# Load_Cell_Biasing.net
KiCad netlist of a schematic drawn in Altium Designer
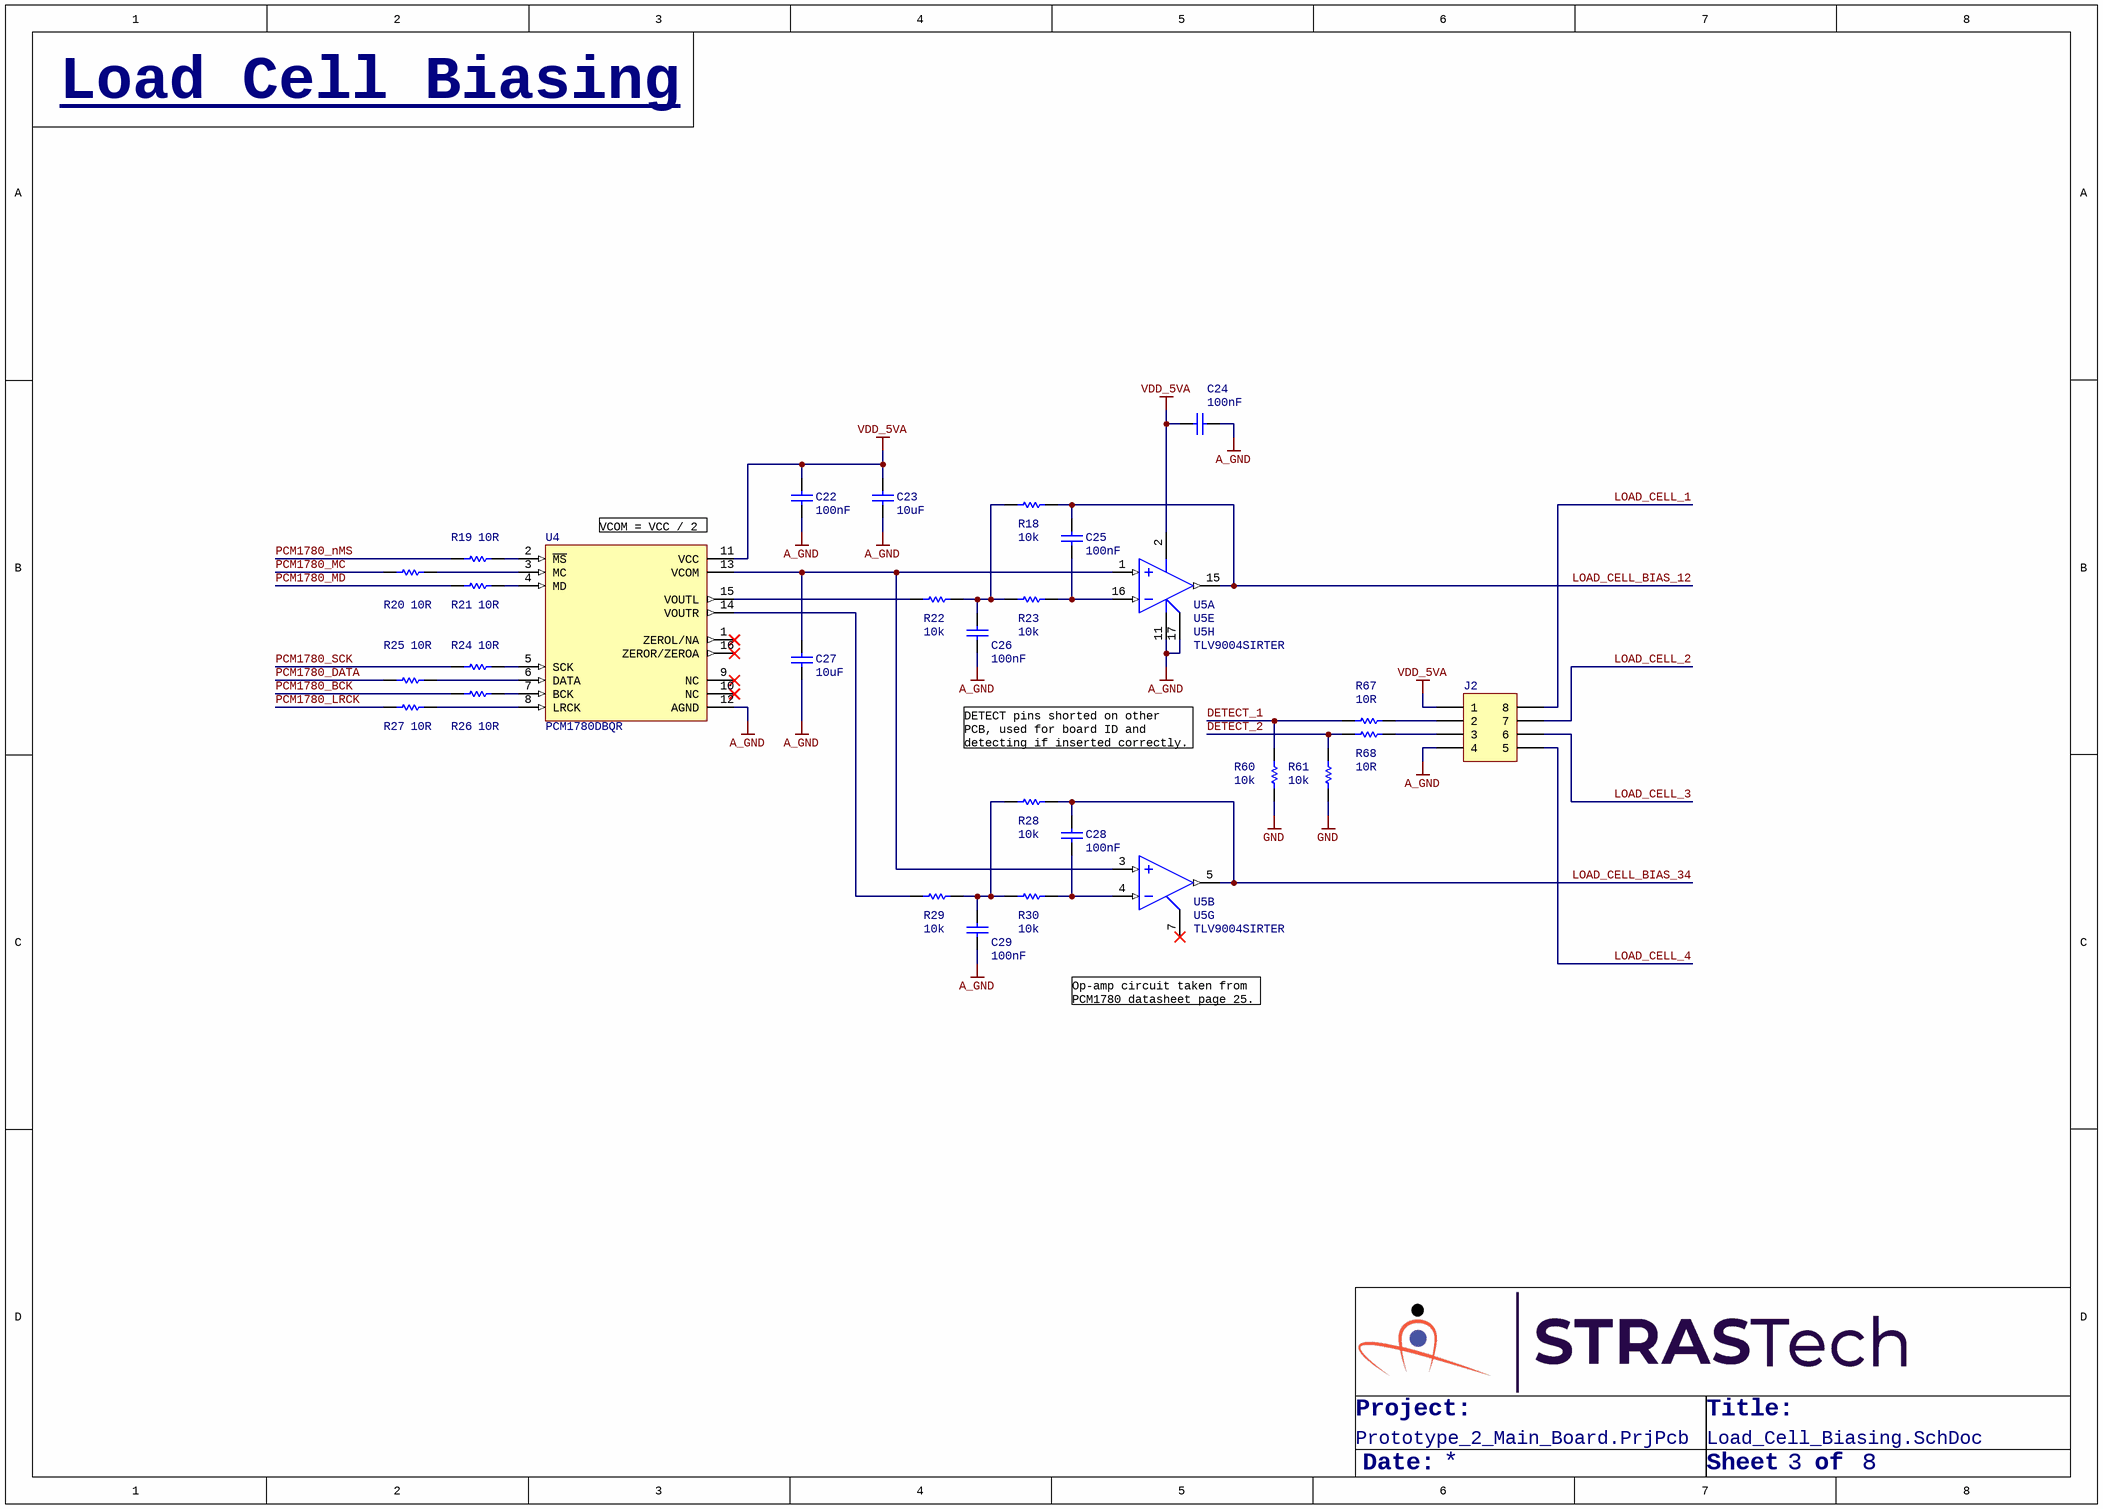
[diagram p0: Load_Cell_Biasing.SchDoc]

(export (version "E")
  (design (tool "Eeschema 10.0.6"))
  (components
    (comp (ref "C22")
      (value "100nF")
      (footprint "Cap,SMD,0402")
      (description "0.1µF ±10% 25V Ceramic Capacitor X7R 0402 (1005 Metric)")
      (fields
        (field (name "VENDOR PART NUMBER") "490-14603-1-ND")
        (field (name "MANUFACTURER") "Murata Electronics")
        (field (name "CREATEDBY") "Judd Foster")
      )
      (libsource (lib "symbols") (part "CAP,Cer,100nF,25VDC,X7R,0402"))
    )
    (comp (ref "C23")
      (value "10uF")
      (footprint "Cap,SMD,0402")
      (description "10 µF ±20% 10V Ceramic Capacitor X5R 0402 (1005 Metric)")
      (fields
        (field (name "VENDOR PART NUMBER") "1276-1450-1-ND")
        (field (name "MANUFACTURER") "Samsung Electro-Mechanics")
        (field (name "CREATEDBY") "Judd Foster")
      )
      (libsource (lib "symbols") (part "CAP,Cer,10uF,10VDC,X5R,0402"))
    )
    (comp (ref "C24")
      (value "100nF")
      (footprint "Cap,SMD,0402")
      (description "0.1µF ±10% 25V Ceramic Capacitor X7R 0402 (1005 Metric)")
      (fields
        (field (name "VENDOR PART NUMBER") "490-14603-1-ND")
        (field (name "MANUFACTURER") "Murata Electronics")
        (field (name "CREATEDBY") "Judd Foster")
      )
      (libsource (lib "symbols") (part "CAP,Cer,100nF,25VDC,X7R,0402"))
    )
    (comp (ref "C25")
      (value "100nF")
      (footprint "Cap,SMD,0402")
      (description "0.1µF ±10% 25V Ceramic Capacitor X7R 0402 (1005 Metric)")
      (fields
        (field (name "VENDOR PART NUMBER") "490-14603-1-ND")
        (field (name "MANUFACTURER") "Murata Electronics")
        (field (name "CREATEDBY") "Judd Foster")
      )
      (libsource (lib "symbols") (part "CAP,Cer,100nF,25VDC,X7R,0402"))
    )
    (comp (ref "C26")
      (value "100nF")
      (footprint "Cap,SMD,0402")
      (description "0.1µF ±10% 25V Ceramic Capacitor X7R 0402 (1005 Metric)")
      (fields
        (field (name "VENDOR PART NUMBER") "490-14603-1-ND")
        (field (name "MANUFACTURER") "Murata Electronics")
        (field (name "CREATEDBY") "Judd Foster")
      )
      (libsource (lib "symbols") (part "CAP,Cer,100nF,25VDC,X7R,0402"))
    )
    (comp (ref "C27")
      (value "10uF")
      (footprint "Cap,SMD,0402")
      (description "10 µF ±20% 10V Ceramic Capacitor X5R 0402 (1005 Metric)")
      (fields
        (field (name "VENDOR PART NUMBER") "1276-1450-1-ND")
        (field (name "MANUFACTURER") "Samsung Electro-Mechanics")
        (field (name "CREATEDBY") "Judd Foster")
      )
      (libsource (lib "symbols") (part "CAP,Cer,10uF,10VDC,X5R,0402"))
    )
    (comp (ref "C28")
      (value "100nF")
      (footprint "Cap,SMD,0402")
      (description "0.1µF ±10% 25V Ceramic Capacitor X7R 0402 (1005 Metric)")
      (fields
        (field (name "VENDOR PART NUMBER") "490-14603-1-ND")
        (field (name "MANUFACTURER") "Murata Electronics")
        (field (name "CREATEDBY") "Judd Foster")
      )
      (libsource (lib "symbols") (part "CAP,Cer,100nF,25VDC,X7R,0402"))
    )
    (comp (ref "C29")
      (value "100nF")
      (footprint "Cap,SMD,0402")
      (description "0.1µF ±10% 25V Ceramic Capacitor X7R 0402 (1005 Metric)")
      (fields
        (field (name "VENDOR PART NUMBER") "490-14603-1-ND")
        (field (name "MANUFACTURER") "Murata Electronics")
        (field (name "CREATEDBY") "Judd Foster")
      )
      (libsource (lib "symbols") (part "CAP,Cer,100nF,25VDC,X7R,0402"))
    )
    (comp (ref "J2")
      (value "Conn,Spring,Piston,8Pos,Thru")
      (footprint "Conn,Spring,Piston,8Pos,Thru")
      (description "8 Position Spring Piston Connector Through Hole")
      (fields
        (field (name "MANUFACTURER") "Mill-Max Manufacturing Corp.")
        (field (name "MANUFACTURER PART NUMBER") "823-22-008-10-002101")
        (field (name "CREATEDBY") "Judd Foster")
      )
      (libsource (lib "symbols") (part "Conn,Spring,Piston,8Pos,Thru"))
    )
    (comp (ref "R18")
      (value "10k")
      (footprint "RES,0402")
      (description "10 kOhms ±5% 0.063W, 1/16W Chip Resistor 0402 (1005 Metric) Automotive AEC-Q200 Thick Film")
      (fields
        (field (name "VENDOR PART NUMBER") "RMCF0402JT10K0CT-ND")
        (field (name "MANUFACTURER") "Stackpole Electronics Inc")
        (field (name "CREATEDBY") "Judd Foster")
      )
      (libsource (lib "symbols") (part "RES,10k,5%,0.063W,0402"))
    )
    (comp (ref "R19")
      (value "10R")
      (footprint "RES,0402")
      (description "10 Ohms ±1% 0.063W, 1/16W Chip Resistor 0402 (1005 Metric) Automotive AEC-Q200 Thick Film")
      (fields
        (field (name "MANUFACTURER") "Panasonic Electronic Components")
        (field (name "MANUFACTURER PART NUMBER") "ERJ-2RKF10R0X")
        (field (name "CREATEDBY") "Judd Foster")
      )
      (libsource (lib "symbols") (part "RES,10R,1%,0.063W,0402"))
    )
    (comp (ref "R20")
      (value "10R")
      (footprint "RES,0402")
      (description "10 Ohms ±1% 0.063W, 1/16W Chip Resistor 0402 (1005 Metric) Automotive AEC-Q200 Thick Film")
      (fields
        (field (name "MANUFACTURER") "Panasonic Electronic Components")
        (field (name "MANUFACTURER PART NUMBER") "ERJ-2RKF10R0X")
        (field (name "CREATEDBY") "Judd Foster")
      )
      (libsource (lib "symbols") (part "RES,10R,1%,0.063W,0402"))
    )
    (comp (ref "R21")
      (value "10R")
      (footprint "RES,0402")
      (description "10 Ohms ±1% 0.063W, 1/16W Chip Resistor 0402 (1005 Metric) Automotive AEC-Q200 Thick Film")
      (fields
        (field (name "MANUFACTURER") "Panasonic Electronic Components")
        (field (name "MANUFACTURER PART NUMBER") "ERJ-2RKF10R0X")
        (field (name "CREATEDBY") "Judd Foster")
      )
      (libsource (lib "symbols") (part "RES,10R,1%,0.063W,0402"))
    )
    (comp (ref "R22")
      (value "10k")
      (footprint "RES,0402")
      (description "10 kOhms ±5% 0.063W, 1/16W Chip Resistor 0402 (1005 Metric) Automotive AEC-Q200 Thick Film")
      (fields
        (field (name "VENDOR PART NUMBER") "RMCF0402JT10K0CT-ND")
        (field (name "MANUFACTURER") "Stackpole Electronics Inc")
        (field (name "CREATEDBY") "Judd Foster")
      )
      (libsource (lib "symbols") (part "RES,10k,5%,0.063W,0402"))
    )
    (comp (ref "R23")
      (value "10k")
      (footprint "RES,0402")
      (description "10 kOhms ±5% 0.063W, 1/16W Chip Resistor 0402 (1005 Metric) Automotive AEC-Q200 Thick Film")
      (fields
        (field (name "VENDOR PART NUMBER") "RMCF0402JT10K0CT-ND")
        (field (name "MANUFACTURER") "Stackpole Electronics Inc")
        (field (name "CREATEDBY") "Judd Foster")
      )
      (libsource (lib "symbols") (part "RES,10k,5%,0.063W,0402"))
    )
    (comp (ref "R24")
      (value "10R")
      (footprint "RES,0402")
      (description "10 Ohms ±1% 0.063W, 1/16W Chip Resistor 0402 (1005 Metric) Automotive AEC-Q200 Thick Film")
      (fields
        (field (name "MANUFACTURER") "Panasonic Electronic Components")
        (field (name "MANUFACTURER PART NUMBER") "ERJ-2RKF10R0X")
        (field (name "CREATEDBY") "Judd Foster")
      )
      (libsource (lib "symbols") (part "RES,10R,1%,0.063W,0402"))
    )
    (comp (ref "R25")
      (value "10R")
      (footprint "RES,0402")
      (description "10 Ohms ±1% 0.063W, 1/16W Chip Resistor 0402 (1005 Metric) Automotive AEC-Q200 Thick Film")
      (fields
        (field (name "MANUFACTURER") "Panasonic Electronic Components")
        (field (name "MANUFACTURER PART NUMBER") "ERJ-2RKF10R0X")
        (field (name "CREATEDBY") "Judd Foster")
      )
      (libsource (lib "symbols") (part "RES,10R,1%,0.063W,0402"))
    )
    (comp (ref "R26")
      (value "10R")
      (footprint "RES,0402")
      (description "10 Ohms ±1% 0.063W, 1/16W Chip Resistor 0402 (1005 Metric) Automotive AEC-Q200 Thick Film")
      (fields
        (field (name "MANUFACTURER") "Panasonic Electronic Components")
        (field (name "MANUFACTURER PART NUMBER") "ERJ-2RKF10R0X")
        (field (name "CREATEDBY") "Judd Foster")
      )
      (libsource (lib "symbols") (part "RES,10R,1%,0.063W,0402"))
    )
    (comp (ref "R27")
      (value "10R")
      (footprint "RES,0402")
      (description "10 Ohms ±1% 0.063W, 1/16W Chip Resistor 0402 (1005 Metric) Automotive AEC-Q200 Thick Film")
      (fields
        (field (name "MANUFACTURER") "Panasonic Electronic Components")
        (field (name "MANUFACTURER PART NUMBER") "ERJ-2RKF10R0X")
        (field (name "CREATEDBY") "Judd Foster")
      )
      (libsource (lib "symbols") (part "RES,10R,1%,0.063W,0402"))
    )
    (comp (ref "R28")
      (value "10k")
      (footprint "RES,0402")
      (description "10 kOhms ±5% 0.063W, 1/16W Chip Resistor 0402 (1005 Metric) Automotive AEC-Q200 Thick Film")
      (fields
        (field (name "VENDOR PART NUMBER") "RMCF0402JT10K0CT-ND")
        (field (name "MANUFACTURER") "Stackpole Electronics Inc")
        (field (name "CREATEDBY") "Judd Foster")
      )
      (libsource (lib "symbols") (part "RES,10k,5%,0.063W,0402"))
    )
    (comp (ref "R29")
      (value "10k")
      (footprint "RES,0402")
      (description "10 kOhms ±5% 0.063W, 1/16W Chip Resistor 0402 (1005 Metric) Automotive AEC-Q200 Thick Film")
      (fields
        (field (name "VENDOR PART NUMBER") "RMCF0402JT10K0CT-ND")
        (field (name "MANUFACTURER") "Stackpole Electronics Inc")
        (field (name "CREATEDBY") "Judd Foster")
      )
      (libsource (lib "symbols") (part "RES,10k,5%,0.063W,0402"))
    )
    (comp (ref "R30")
      (value "10k")
      (footprint "RES,0402")
      (description "10 kOhms ±5% 0.063W, 1/16W Chip Resistor 0402 (1005 Metric) Automotive AEC-Q200 Thick Film")
      (fields
        (field (name "VENDOR PART NUMBER") "RMCF0402JT10K0CT-ND")
        (field (name "MANUFACTURER") "Stackpole Electronics Inc")
        (field (name "CREATEDBY") "Judd Foster")
      )
      (libsource (lib "symbols") (part "RES,10k,5%,0.063W,0402"))
    )
    (comp (ref "R60")
      (value "10k")
      (footprint "RES,0402")
      (description "10 kOhms ±5% 0.063W, 1/16W Chip Resistor 0402 (1005 Metric) Automotive AEC-Q200 Thick Film")
      (fields
        (field (name "VENDOR PART NUMBER") "RMCF0402JT10K0CT-ND")
        (field (name "MANUFACTURER") "Stackpole Electronics Inc")
        (field (name "CREATEDBY") "Judd Foster")
      )
      (libsource (lib "symbols") (part "RES,10k,5%,0.063W,0402"))
    )
    (comp (ref "R61")
      (value "10k")
      (footprint "RES,0402")
      (description "10 kOhms ±5% 0.063W, 1/16W Chip Resistor 0402 (1005 Metric) Automotive AEC-Q200 Thick Film")
      (fields
        (field (name "VENDOR PART NUMBER") "RMCF0402JT10K0CT-ND")
        (field (name "MANUFACTURER") "Stackpole Electronics Inc")
        (field (name "CREATEDBY") "Judd Foster")
      )
      (libsource (lib "symbols") (part "RES,10k,5%,0.063W,0402"))
    )
    (comp (ref "R67")
      (value "10R")
      (footprint "RES,0402")
      (description "10 Ohms ±1% 0.063W, 1/16W Chip Resistor 0402 (1005 Metric) Automotive AEC-Q200 Thick Film")
      (fields
        (field (name "MANUFACTURER") "Panasonic Electronic Components")
        (field (name "MANUFACTURER PART NUMBER") "ERJ-2RKF10R0X")
        (field (name "CREATEDBY") "Judd Foster")
      )
      (libsource (lib "symbols") (part "RES,10R,1%,0.063W,0402"))
    )
    (comp (ref "R68")
      (value "10R")
      (footprint "RES,0402")
      (description "10 Ohms ±1% 0.063W, 1/16W Chip Resistor 0402 (1005 Metric) Automotive AEC-Q200 Thick Film")
      (fields
        (field (name "MANUFACTURER") "Panasonic Electronic Components")
        (field (name "MANUFACTURER PART NUMBER") "ERJ-2RKF10R0X")
        (field (name "CREATEDBY") "Judd Foster")
      )
      (libsource (lib "symbols") (part "RES,10R,1%,0.063W,0402"))
    )
    (comp (ref "U4")
      (value "PCM1780DBQR")
      (footprint "IC,TSSOP-16,W3.9,P0.635MM")
      (description "DAC, Audio 24 b 200k I²S 16-SSOP")
      (fields
        (field (name "MANUFACTURER") "Texas Instruments")
        (field (name "VENDOR PART NUMBER") "296-41373-1-ND")
        (field (name "CREATEDBY") "Judd Foster")
      )
      (libsource (lib "symbols") (part "PCM1780DBQR"))
    )
    (comp (ref "U5")
      (value "TLV9004SIRTER")
      (footprint "IC,QFN-16,3x3")
      (description "General Purpose Amplifier 4 Circuit Rail-to-Rail 16-WQFN (3x3)")
      (fields
        (field (name "MANUFACTURER") "Texas Instruments")
        (field (name "VENDOR PART NUMBER") "296-51829-1-ND")
        (field (name "CREATEDBY") "Judd Foster")
      )
      (libsource (lib "symbols") (part "TLV9004SIRTER"))
    )
  )
  (nets
    (net (code "1") (name "/DETECT_1") (class "Default")
      (node (ref "R60") (pin "2") (pinfunction "2_2") (pintype "passive"))
      (node (ref "R67") (pin "1") (pinfunction "1_1") (pintype "passive"))
    )
    (net (code "2") (name "/DETECT_2") (class "Default")
      (node (ref "R61") (pin "2") (pinfunction "2_2") (pintype "passive"))
      (node (ref "R68") (pin "1") (pinfunction "1_1") (pintype "passive"))
    )
    (net (code "3") (name "/LOAD_CELL_1") (class "Default")
      (node (ref "J2") (pin "8") (pinfunction "8_8") (pintype "passive"))
    )
    (net (code "4") (name "/LOAD_CELL_2") (class "Default")
      (node (ref "J2") (pin "7") (pinfunction "7_7") (pintype "passive"))
    )
    (net (code "5") (name "/LOAD_CELL_3") (class "Default")
      (node (ref "J2") (pin "6") (pinfunction "6_6") (pintype "passive"))
    )
    (net (code "6") (name "/LOAD_CELL_4") (class "Default")
      (node (ref "J2") (pin "5") (pinfunction "5_5") (pintype "passive"))
    )
    (net (code "7") (name "/LOAD_CELL_BIAS_12") (class "Default")
      (node (ref "C25") (pin "2") (pinfunction "2_2") (pintype "passive"))
      (node (ref "R18") (pin "1") (pinfunction "1_1") (pintype "passive"))
      (node (ref "U5") (pin "15") (pinfunction "OUT1_15") (pintype "output"))
    )
    (net (code "8") (name "/LOAD_CELL_BIAS_34") (class "Default")
      (node (ref "C28") (pin "2") (pinfunction "2_2") (pintype "passive"))
      (node (ref "R28") (pin "1") (pinfunction "1_1") (pintype "passive"))
      (node (ref "U5") (pin "5") (pinfunction "OUT2_5") (pintype "output"))
    )
    (net (code "9") (name "/PCM1780_BCK") (class "Default")
      (node (ref "R26") (pin "1") (pinfunction "1_1") (pintype "passive"))
    )
    (net (code "10") (name "/PCM1780_DATA") (class "Default")
      (node (ref "R25") (pin "1") (pinfunction "1_1") (pintype "passive"))
    )
    (net (code "11") (name "/PCM1780_LRCK") (class "Default")
      (node (ref "R27") (pin "1") (pinfunction "1_1") (pintype "passive"))
    )
    (net (code "12") (name "/PCM1780_MC") (class "Default")
      (node (ref "R20") (pin "1") (pinfunction "1_1") (pintype "passive"))
    )
    (net (code "13") (name "/PCM1780_MD") (class "Default")
      (node (ref "R21") (pin "1") (pinfunction "1_1") (pintype "passive"))
    )
    (net (code "14") (name "/PCM1780_SCK") (class "Default")
      (node (ref "R24") (pin "1") (pinfunction "1_1") (pintype "passive"))
    )
    (net (code "15") (name "/PCM1780_nMS") (class "Default")
      (node (ref "R19") (pin "1") (pinfunction "1_1") (pintype "passive"))
    )
    (net (code "16") (name "A_GND") (class "Default")
      (node (ref "C22") (pin "1") (pinfunction "1_1") (pintype "passive"))
      (node (ref "C23") (pin "1") (pinfunction "1_1") (pintype "passive"))
      (node (ref "C24") (pin "1") (pinfunction "1_1") (pintype "passive"))
      (node (ref "C26") (pin "1") (pinfunction "1_1") (pintype "passive"))
      (node (ref "C27") (pin "2") (pinfunction "2_2") (pintype "passive"))
      (node (ref "C29") (pin "1") (pinfunction "1_1") (pintype "passive"))
      (node (ref "J2") (pin "4") (pinfunction "4_4") (pintype "passive"))
      (node (ref "U4") (pin "12") (pinfunction "AGND_12") (pintype "power_in"))
      (node (ref "U5") (pin "11") (pinfunction "V-_11") (pintype "power_in"))
      (node (ref "U5") (pin "17") (pinfunction "PAD_17") (pintype "power_in"))
    )
    (net (code "17") (name "GND") (class "Default")
      (node (ref "R60") (pin "1") (pinfunction "1_1") (pintype "passive"))
      (node (ref "R61") (pin "1") (pinfunction "1_1") (pintype "passive"))
    )
    (net (code "18") (name "Net-(C26-Pad2)") (class "Default")
      (node (ref "C26") (pin "2") (pinfunction "2_2") (pintype "passive"))
      (node (ref "R18") (pin "2") (pinfunction "2_2") (pintype "passive"))
      (node (ref "R22") (pin "2") (pinfunction "2_2") (pintype "passive"))
      (node (ref "R23") (pin "1") (pinfunction "1_1") (pintype "passive"))
    )
    (net (code "19") (name "Net-(C29-Pad2)") (class "Default")
      (node (ref "C29") (pin "2") (pinfunction "2_2") (pintype "passive"))
      (node (ref "R28") (pin "2") (pinfunction "2_2") (pintype "passive"))
      (node (ref "R29") (pin "2") (pinfunction "2_2") (pintype "passive"))
      (node (ref "R30") (pin "1") (pinfunction "1_1") (pintype "passive"))
    )
    (net (code "20") (name "Net-(J2-Pad2)") (class "Default")
      (node (ref "J2") (pin "2") (pinfunction "2_2") (pintype "passive"))
      (node (ref "R67") (pin "2") (pinfunction "2_2") (pintype "passive"))
    )
    (net (code "21") (name "Net-(J2-Pad3)") (class "Default")
      (node (ref "J2") (pin "3") (pinfunction "3_3") (pintype "passive"))
      (node (ref "R68") (pin "2") (pinfunction "2_2") (pintype "passive"))
    )
    (net (code "22") (name "Net-(U4-BCK)") (class "Default")
      (node (ref "R26") (pin "2") (pinfunction "2_2") (pintype "passive"))
      (node (ref "U4") (pin "7") (pinfunction "BCK_7") (pintype "input"))
    )
    (net (code "23") (name "Net-(U4-DATA)") (class "Default")
      (node (ref "R25") (pin "2") (pinfunction "2_2") (pintype "passive"))
      (node (ref "U4") (pin "6") (pinfunction "DATA_6") (pintype "input"))
    )
    (net (code "24") (name "Net-(U4-LRCK)") (class "Default")
      (node (ref "R27") (pin "2") (pinfunction "2_2") (pintype "passive"))
      (node (ref "U4") (pin "8") (pinfunction "LRCK_8") (pintype "input"))
    )
    (net (code "25") (name "Net-(U4-MC)") (class "Default")
      (node (ref "R20") (pin "2") (pinfunction "2_2") (pintype "passive"))
      (node (ref "U4") (pin "3") (pinfunction "MC_3") (pintype "input"))
    )
    (net (code "26") (name "Net-(U4-MD)") (class "Default")
      (node (ref "R21") (pin "2") (pinfunction "2_2") (pintype "passive"))
      (node (ref "U4") (pin "4") (pinfunction "MD_4") (pintype "input"))
    )
    (net (code "27") (name "Net-(U4-SCK)") (class "Default")
      (node (ref "R24") (pin "2") (pinfunction "2_2") (pintype "passive"))
      (node (ref "U4") (pin "5") (pinfunction "SCK_5") (pintype "input"))
    )
    (net (code "28") (name "Net-(U4-VCOM)") (class "Default")
      (node (ref "C27") (pin "1") (pinfunction "1_1") (pintype "passive"))
      (node (ref "U4") (pin "13") (pinfunction "VCOM_13") (pintype "power_in"))
      (node (ref "U5") (pin "1") (pinfunction "IN1+_1") (pintype "input"))
      (node (ref "U5") (pin "3") (pinfunction "IN2+_3") (pintype "input"))
    )
    (net (code "29") (name "Net-(U4-VOUTL)") (class "Default")
      (node (ref "R22") (pin "1") (pinfunction "1_1") (pintype "passive"))
      (node (ref "U4") (pin "15") (pinfunction "VOUTL_15") (pintype "output"))
    )
    (net (code "30") (name "Net-(U4-VOUTR)") (class "Default")
      (node (ref "R29") (pin "1") (pinfunction "1_1") (pintype "passive"))
      (node (ref "U4") (pin "14") (pinfunction "VOUTR_14") (pintype "output"))
    )
    (net (code "31") (name "Net-(U4-~{MS})") (class "Default")
      (node (ref "R19") (pin "2") (pinfunction "2_2") (pintype "passive"))
      (node (ref "U4") (pin "2") (pinfunction "~{MS}_2") (pintype "input"))
    )
    (net (code "32") (name "Net-(U5A-IN1-)") (class "Default")
      (node (ref "C25") (pin "1") (pinfunction "1_1") (pintype "passive"))
      (node (ref "R23") (pin "2") (pinfunction "2_2") (pintype "passive"))
      (node (ref "U5") (pin "16") (pinfunction "IN1-_16") (pintype "input"))
    )
    (net (code "33") (name "Net-(U5B-IN2-)") (class "Default")
      (node (ref "C28") (pin "1") (pinfunction "1_1") (pintype "passive"))
      (node (ref "R30") (pin "2") (pinfunction "2_2") (pintype "passive"))
      (node (ref "U5") (pin "4") (pinfunction "IN2-_4") (pintype "input"))
    )
    (net (code "34") (name "VDD_5VA") (class "Default")
      (node (ref "C22") (pin "2") (pinfunction "2_2") (pintype "passive"))
      (node (ref "C23") (pin "2") (pinfunction "2_2") (pintype "passive"))
      (node (ref "C24") (pin "2") (pinfunction "2_2") (pintype "passive"))
      (node (ref "J2") (pin "1") (pinfunction "1_1") (pintype "passive"))
      (node (ref "U4") (pin "11") (pinfunction "VCC_11") (pintype "power_in"))
      (node (ref "U5") (pin "2") (pinfunction "V+_2") (pintype "power_in"))
    )
    (net (code "35") (name "unconnected-(U4-NC-Pad9)") (class "Default")
      (node (ref "U4") (pin "9") (pinfunction "NC_9") (pintype "passive+no_connect"))
    )
    (net (code "36") (name "unconnected-(U4-NC-Pad10)") (class "Default")
      (node (ref "U4") (pin "10") (pinfunction "NC_10") (pintype "passive+no_connect"))
    )
    (net (code "37") (name "unconnected-(U4-ZEROL{slash}NA-Pad1)") (class "Default")
      (node (ref "U4") (pin "1") (pinfunction "ZEROL/NA_1") (pintype "output+no_connect"))
    )
    (net (code "38") (name "unconnected-(U4-ZEROR{slash}ZEROA-Pad16)") (class "Default")
      (node (ref "U4") (pin "16") (pinfunction "ZEROR/ZEROA_16") (pintype "output+no_connect"))
    )
    (net (code "39") (name "unconnected-(U5G-~{SHDN}34-Pad7)") (class "Default")
      (node (ref "U5") (pin "7") (pinfunction "~{SHDN}34_7") (pintype "power_in+no_connect"))
    )
  )
)
